# MezzanineConnectors_Cortes.net
KiCad netlist of a schematic drawn in Altium Designer
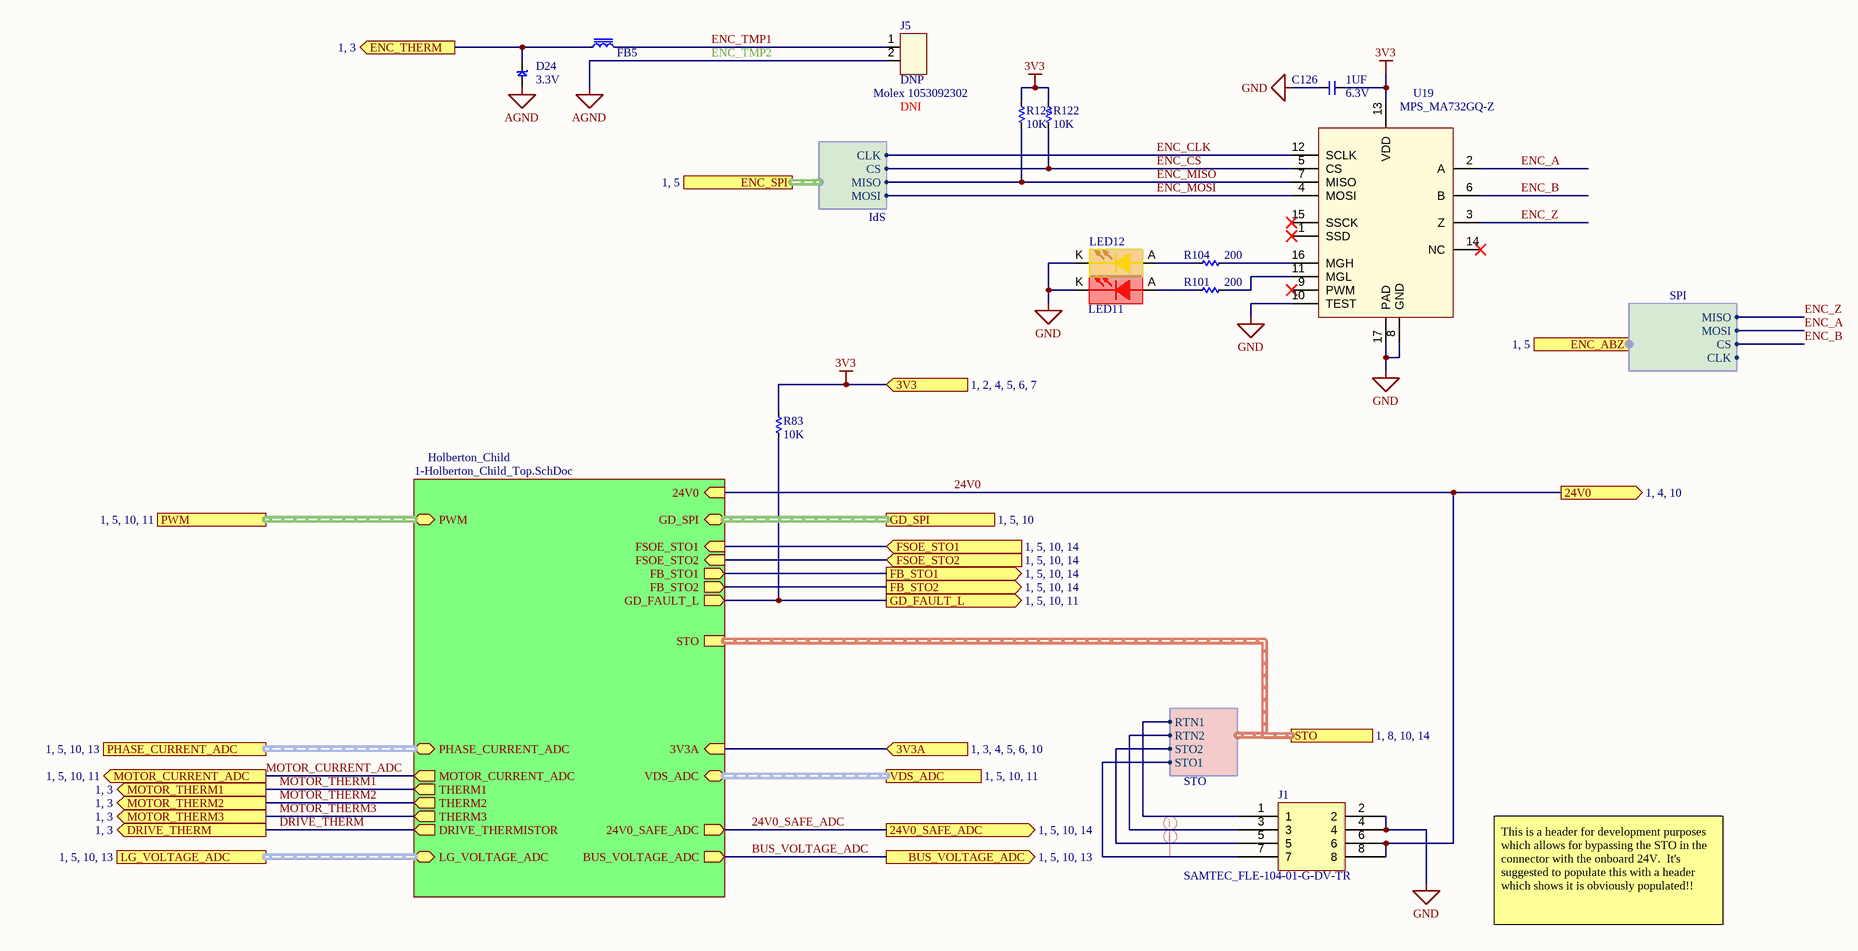
[diagram p0: MezzanineConnectors_Cortes.SchDoc]

(export (version "E")
  (design (tool "Eeschema 10.0.6"))
  (components
    (comp (ref "C126")
      (value "1UF")
      (footprint "C0201")
      (description "CAP, CER, X5R, 1uF, 6.3V, 20%, 0201, 0.33mm T")
      (fields
        (field (name "MFG") "SAMSUNG")
        (field (name "VOLTAGE") "6.3V")
        (field (name "Comment") "__Template_Cap")
      )
      (libsource (lib "AltiumReleaseLibDB") (part "__Template_Cap"))
    )
    (comp (ref "D24")
      (value "3.3V")
      (footprint "SOD1060X40")
      (description "TVS, DIODE, UNIDIR, 3.3VRWM, 4.8VBR, 7.8VCL, SOD-923")
      (fields (field (name "MFG") "ON Semiconductor"))
      (libsource (lib "AltiumReleaseLibDB") (part "__Template_Diode_TVS_A/K"))
    )
    (comp (ref "FB5")
      (value "LAIRD MI0603L221R-10")
      (footprint "INDC160X80X105L30N")
      (description "FERRITE BEAD 220 OHM 0603 1LN")
      (fields (field (name "MFG") "Laird-Signal Integrity Products"))
      (libsource (lib "MiscSch1") (part "LAIRD_MI0603L221R-10"))
    )
    (comp (ref "J1")
      (value "SAMTEC_FLE-104-01-G-DV-TR")
      (footprint "SAMTEC_FLE-104-01-G-DV-TR")
      (description "CONN RCPT .05\" 8POS DUAL SMD")
      (fields (field (name "MFG") "Samtec Inc."))
      (libsource (lib "MiscSch1") (part "SAMTEC_FLE-104-01-G-DV-TR"))
    )
    (comp (ref "J5")
      (value "DNP")
      (footprint "Molex 1053092302")
      (description "CONN HEADER VERT 2POS 2.5MM")
      (fields
        (field (name "MFG") "Molex")
        (field (name "ALTIUM_VALUE") "Molex 1053092302")
        (field (name "DNI") "DNI")
      )
      (libsource (lib "MiscSch1") (part "Molex 1053092302"))
    )
    (comp (ref "LED11")
      (value "APHHS1005SURCK")
      (footprint "LED_APHHS1005SURCK")
      (description "LED RED CLEAR CHIP SMD")
      (fields (field (name "MFG") "Kingbright"))
      (libsource (lib "Cortes_Gebru_v05_Rev03_1") (part "APHHS1005SURCK"))
    )
    (comp (ref "LED12")
      (value "SML-P11DTT86R")
      (footprint "LED_SML-P11DTT86R")
      (description "LED ORANGE CLEAR 1006 SMD")
      (fields (field (name "MFG") "Rohm Semiconductor"))
      (libsource (lib "Cortes_Gebru_v05_Rev03_1") (part "SML-P11DTT86R"))
    )
    (comp (ref "R83")
      (value "10K")
      (footprint "R0201")
      (description "RES, 10K, 1%, 1/20W, 0201, AUTOGRADE")
      (fields (field (name "MFG") "PANASONIC") (field (name "Comment") "__Template_Resistor"))
      (libsource (lib "AltiumReleaseLibDB") (part "__Template_Resistor"))
    )
    (comp (ref "R101")
      (value "200")
      (footprint "R0201")
      (description "RES, 200, 1%, 1/20W, 0201, AUTOGRADE")
      (fields (field (name "MFG") "Panasonic Electronic Components"))
      (libsource (lib "AltiumReleaseLibDB") (part "__Template_Resistor"))
    )
    (comp (ref "R104")
      (value "200")
      (footprint "R0201")
      (description "RES, 200, 1%, 1/20W, 0201, AUTOGRADE")
      (fields (field (name "MFG") "Panasonic Electronic Components"))
      (libsource (lib "AltiumReleaseLibDB") (part "__Template_Resistor"))
    )
    (comp (ref "R122")
      (value "10K")
      (footprint "R0201")
      (description "RES, 10K, 1%, 1/20W, 0201, AUTOGRADE")
      (fields (field (name "MFG") "PANASONIC") (field (name "Comment") "__Template_Resistor"))
      (libsource (lib "AltiumReleaseLibDB") (part "__Template_Resistor"))
    )
    (comp (ref "R123")
      (value "10K")
      (footprint "R0201")
      (description "RES, 10K, 1%, 1/20W, 0201, AUTOGRADE")
      (fields (field (name "MFG") "PANASONIC") (field (name "Comment") "__Template_Resistor"))
      (libsource (lib "AltiumReleaseLibDB") (part "__Template_Resistor"))
    )
    (comp (ref "U19")
      (value "MPS_MA732GQ-Z")
      (footprint "MPS_MA732GQ-Z")
      (description "14-BIT, DIGITAL, CONTACTLESS ANG")
      (fields (field (name "MFG") "Monolithic Power Systems Inc."))
      (libsource (lib "MiscSch1") (part "MPS_MA732GQ-Z"))
    )
  )
  (nets
    (net (code "9") (name "/24V0") (class "Default")
      (node (ref "J1") (pin "6") (pinfunction "6_6") (pintype "passive"))
      (node (ref "J1") (pin "8") (pinfunction "8_8") (pintype "passive"))
    )
    (net (code "13") (name "/ENC_A") (class "Default")
      (node (ref "U19") (pin "2") (pinfunction "A_2") (pintype "passive"))
    )
    (net (code "14") (name "/ENC_B") (class "Default")
      (node (ref "U19") (pin "6") (pinfunction "B_6") (pintype "passive"))
    )
    (net (code "15") (name "/ENC_CLK") (class "Default")
      (node (ref "U19") (pin "12") (pinfunction "SCLK_12") (pintype "passive"))
    )
    (net (code "16") (name "/ENC_CS") (class "Default")
      (node (ref "R122") (pin "1") (pintype "passive"))
      (node (ref "U19") (pin "5") (pinfunction "CS_5") (pintype "passive"))
    )
    (net (code "17") (name "/ENC_MISO") (class "Default")
      (node (ref "R123") (pin "1") (pintype "passive"))
      (node (ref "U19") (pin "7") (pinfunction "MISO_7") (pintype "passive"))
    )
    (net (code "18") (name "/ENC_MOSI") (class "Default")
      (node (ref "U19") (pin "4") (pinfunction "MOSI_4") (pintype "passive"))
    )
    (net (code "19") (name "/ENC_THERM") (class "Default")
      (node (ref "D24") (pin "K") (pinfunction "K_K") (pintype "passive"))
      (node (ref "FB5") (pin "1") (pintype "passive"))
    )
    (net (code "20") (name "/ENC_TMP1") (class "Default")
      (node (ref "FB5") (pin "2") (pintype "passive"))
      (node (ref "J5") (pin "1") (pinfunction "1_1") (pintype "passive"))
    )
    (net (code "21") (name "/ENC_Z") (class "Default")
      (node (ref "U19") (pin "3") (pinfunction "Z_3") (pintype "passive"))
    )
    (net (code "26") (name "/GD_FAULT_L") (class "Default") (node (ref "R83") (pin "1") (pintype "passive")))
    (net (code "35") (name "/RTN1") (class "Default")
      (node (ref "J1") (pin "1") (pinfunction "1_1") (pintype "passive"))
    )
    (net (code "36") (name "/RTN2") (class "Default")
      (node (ref "J1") (pin "3") (pinfunction "3_3") (pintype "passive"))
    )
    (net (code "37") (name "/STO1") (class "Default")
      (node (ref "J1") (pin "7") (pinfunction "7_7") (pintype "passive"))
    )
    (net (code "38") (name "/STO2") (class "Default")
      (node (ref "J1") (pin "5") (pinfunction "5_5") (pintype "passive"))
    )
    (net (code "42") (name "3V3") (class "Default")
      (node (ref "C126") (pin "2") (pintype "passive"))
      (node (ref "R122") (pin "2") (pintype "passive"))
      (node (ref "R123") (pin "2") (pintype "passive"))
      (node (ref "R83") (pin "2") (pintype "passive"))
      (node (ref "U19") (pin "13") (pinfunction "VDD_13") (pintype "passive"))
    )
    (net (code "43") (name "AGND") (class "Default")
      (node (ref "D24") (pin "A") (pinfunction "A_A") (pintype "passive"))
      (node (ref "J5") (pin "2") (pinfunction "2_2") (pintype "passive"))
    )
    (net (code "44") (name "GND") (class "Default")
      (node (ref "C126") (pin "1") (pintype "passive"))
      (node (ref "J1") (pin "2") (pinfunction "2_2") (pintype "passive"))
      (node (ref "J1") (pin "4") (pinfunction "4_4") (pintype "passive"))
      (node (ref "LED11") (pin "K") (pinfunction "K_K") (pintype "passive"))
      (node (ref "LED12") (pin "K") (pinfunction "K_K") (pintype "passive"))
      (node (ref "U19") (pin "10") (pinfunction "TEST_10") (pintype "passive"))
      (node (ref "U19") (pin "17") (pinfunction "PAD_17") (pintype "passive"))
      (node (ref "U19") (pin "8") (pinfunction "GND_8") (pintype "passive"))
    )
    (net (code "45") (name "Net-(LED11-PadA)") (class "Default")
      (node (ref "LED11") (pin "A") (pinfunction "A_A") (pintype "passive"))
      (node (ref "R101") (pin "2") (pintype "passive"))
    )
    (net (code "46") (name "Net-(LED12-PadA)") (class "Default")
      (node (ref "LED12") (pin "A") (pinfunction "A_A") (pintype "passive"))
      (node (ref "R104") (pin "2") (pintype "passive"))
    )
    (net (code "47") (name "Net-(U19-MGH)") (class "Default")
      (node (ref "R104") (pin "1") (pintype "passive"))
      (node (ref "U19") (pin "16") (pinfunction "MGH_16") (pintype "passive"))
    )
    (net (code "48") (name "Net-(U19-MGL)") (class "Default")
      (node (ref "R101") (pin "1") (pintype "passive"))
      (node (ref "U19") (pin "11") (pinfunction "MGL_11") (pintype "passive"))
    )
    (net (code "49") (name "unconnected-(U19-NC-Pad14)") (class "Default")
      (node (ref "U19") (pin "14") (pinfunction "NC_14") (pintype "passive+no_connect"))
    )
    (net (code "50") (name "unconnected-(U19-PWM-Pad9)") (class "Default")
      (node (ref "U19") (pin "9") (pinfunction "PWM_9") (pintype "passive+no_connect"))
    )
    (net (code "51") (name "unconnected-(U19-SSCK-Pad15)") (class "Default")
      (node (ref "U19") (pin "15") (pinfunction "SSCK_15") (pintype "passive+no_connect"))
    )
    (net (code "52") (name "unconnected-(U19-SSD-Pad1)") (class "Default")
      (node (ref "U19") (pin "1") (pinfunction "SSD_1") (pintype "passive+no_connect"))
    )
  )
)
